# Sensor_Interface.net
KiCad netlist of a schematic drawn in Altium Designer
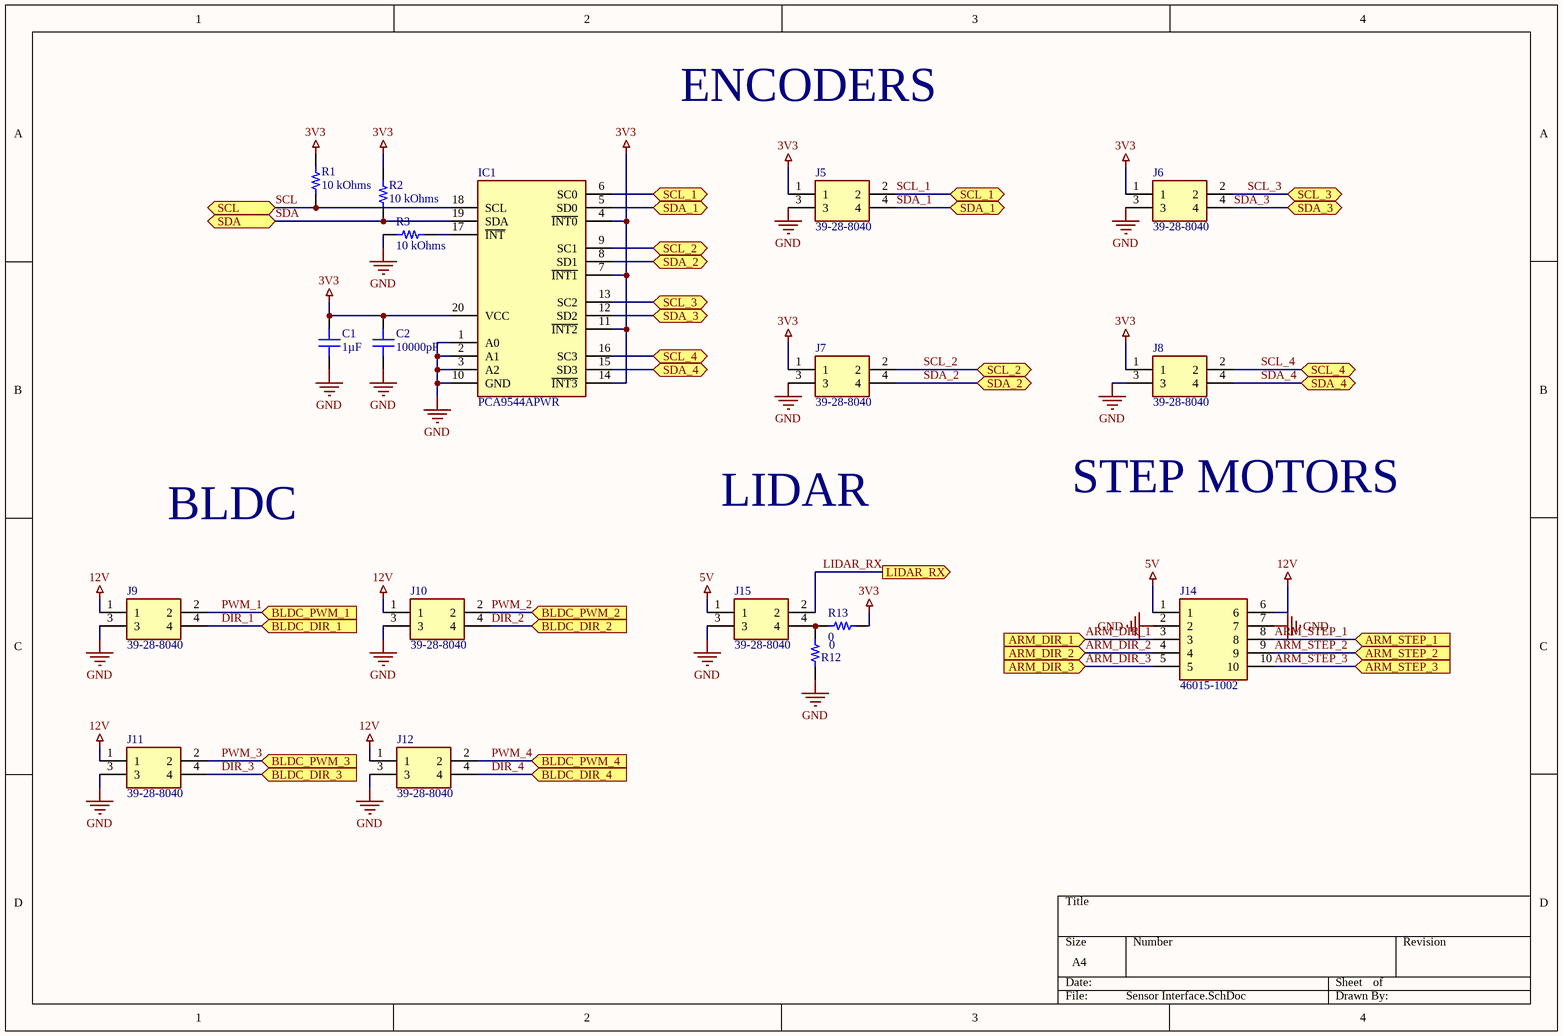
[diagram p0: Sensor Interface.SchDoc]

(export (version "E")
  (design (tool "Eeschema 10.0.6"))
  (components
    (comp (ref "C1")
      (value "1µF")
      (footprint "CAP 0603_1608")
      (description "CAP CER 0603 1UF 16V X7R 10%")
      (fields (field (name "PART NUMBER") "C0603C105K4RACAUTO") (field (name "MANUFACTURER") "KEMET"))
      (libsource (lib "Celestial Altium Library - altium_library") (part "Capacitor"))
    )
    (comp (ref "C2")
      (value "10000pF")
      (footprint "CAP 0603_1608")
      (description "CAP CER 0603 .01UF 16V X7R 20% A")
      (fields (field (name "PART NUMBER") "C0603C103M4RACAUTO") (field (name "MANUFACTURER") "KEMET"))
      (libsource (lib "Celestial Altium Library - altium_library") (part "Capacitor"))
    )
    (comp (ref "IC1")
      (value "PCA9544APWR")
      (footprint "SamacSys:SOP65P640X120-20N")
      (description "Integrated Circuit")
      (fields (field (name "MOUSER PART NUMBER") "595-PCA9544APWR"))
      (libsource (lib "SamacSys") (part "PCA9544APWR"))
    )
    (comp (ref "J5")
      (value "39-28-8040")
      (footprint "SamacSys:RHDR4W125P550X420_2X2_960X960X1310P")
      (description "Connector")
      (fields (field (name "MOUSER PART NUMBER") "538-39-28-8040"))
      (libsource (lib "SamacSys") (part "39-28-8040"))
    )
    (comp (ref "J6")
      (value "39-28-8040")
      (footprint "SamacSys:RHDR4W125P550X420_2X2_960X960X1310P")
      (description "Connector")
      (fields (field (name "MOUSER PART NUMBER") "538-39-28-8040"))
      (libsource (lib "SamacSys") (part "39-28-8040"))
    )
    (comp (ref "J7")
      (value "39-28-8040")
      (footprint "SamacSys:RHDR4W125P550X420_2X2_960X960X1310P")
      (description "Connector")
      (fields (field (name "MOUSER PART NUMBER") "538-39-28-8040"))
      (libsource (lib "SamacSys") (part "39-28-8040"))
    )
    (comp (ref "J8")
      (value "39-28-8040")
      (footprint "SamacSys:RHDR4W125P550X420_2X2_960X960X1310P")
      (description "Connector")
      (fields (field (name "MOUSER PART NUMBER") "538-39-28-8040"))
      (libsource (lib "SamacSys") (part "39-28-8040"))
    )
    (comp (ref "J9")
      (value "39-28-8040")
      (footprint "SamacSys:RHDR4W125P550X420_2X2_960X960X1310P")
      (description "Connector")
      (fields (field (name "MOUSER PART NUMBER") "538-39-28-8040"))
      (libsource (lib "SamacSys") (part "39-28-8040"))
    )
    (comp (ref "J10")
      (value "39-28-8040")
      (footprint "SamacSys:RHDR4W125P550X420_2X2_960X960X1310P")
      (description "Connector")
      (fields (field (name "MOUSER PART NUMBER") "538-39-28-8040"))
      (libsource (lib "SamacSys") (part "39-28-8040"))
    )
    (comp (ref "J11")
      (value "39-28-8040")
      (footprint "SamacSys:RHDR4W125P550X420_2X2_960X960X1310P")
      (description "Connector")
      (fields (field (name "MOUSER PART NUMBER") "538-39-28-8040"))
      (libsource (lib "SamacSys") (part "39-28-8040"))
    )
    (comp (ref "J12")
      (value "39-28-8040")
      (footprint "SamacSys:RHDR4W125P550X420_2X2_960X960X1310P")
      (description "Connector")
      (fields (field (name "MOUSER PART NUMBER") "538-39-28-8040"))
      (libsource (lib "SamacSys") (part "39-28-8040"))
    )
    (comp (ref "J14")
      (value "46015-1002")
      (footprint "SamacSys:460151002")
      (description "Connector")
      (fields (field (name "MOUSER PART NUMBER") "538-46015-1002"))
      (libsource (lib "SamacSys") (part "46015-1002"))
    )
    (comp (ref "J15")
      (value "39-28-8040")
      (footprint "SamacSys:RHDR4W125P550X420_2X2_960X960X1310P")
      (description "Connector")
      (fields (field (name "MOUSER PART NUMBER") "538-39-28-8040"))
      (libsource (lib "SamacSys") (part "39-28-8040"))
    )
    (comp (ref "R1")
      (value "10 kOhms")
      (footprint "RES 0603_1608")
      (description "RES SMD 10K OHM 1% 1/10W 0603")
      (fields (field (name "PART NUMBER") "AF0603FR-0710KL") (field (name "MANUFACTURER") "Yageo"))
      (libsource (lib "Celestial Altium Library - altium_library") (part "Resistor"))
    )
    (comp (ref "R2")
      (value "10 kOhms")
      (footprint "RES 0603_1608")
      (description "RES SMD 10K OHM 1% 1/10W 0603")
      (fields (field (name "PART NUMBER") "AF0603FR-0710KL") (field (name "MANUFACTURER") "Yageo"))
      (libsource (lib "Celestial Altium Library - altium_library") (part "Resistor"))
    )
    (comp (ref "R3")
      (value "10 kOhms")
      (footprint "RES 0603_1608")
      (description "RES SMD 10K OHM 1% 1/10W 0603")
      (fields (field (name "PART NUMBER") "AF0603FR-0710KL") (field (name "MANUFACTURER") "Yageo"))
      (libsource (lib "Celestial Altium Library - altium_library") (part "Resistor"))
    )
    (comp (ref "R12")
      (value "0")
      (footprint "RES 0603_1608")
      (description "RES 0 OHM JUMPER 0603")
      (fields
        (field (name "PART NUMBER") "TLRZ1JTTD")
        (field (name "MANUFACTURER") "KOA Speer Electronics, Inc.")
      )
      (libsource (lib "Celestial Altium Library - altium_library") (part "Resistor"))
    )
    (comp (ref "R13")
      (value "0")
      (footprint "RES 0603_1608")
      (description "RES 0 OHM JUMPER 0603")
      (fields
        (field (name "PART NUMBER") "TLRZ1JTTD")
        (field (name "MANUFACTURER") "KOA Speer Electronics, Inc.")
      )
      (libsource (lib "Celestial Altium Library - altium_library") (part "Resistor"))
    )
  )
  (nets
    (net (code "1") (name "/ARM_DIR_1") (class "Default")
      (node (ref "J14") (pin "3") (pinfunction "3_3") (pintype "passive"))
    )
    (net (code "2") (name "/ARM_DIR_2") (class "Default")
      (node (ref "J14") (pin "4") (pinfunction "4_4") (pintype "passive"))
    )
    (net (code "3") (name "/ARM_DIR_3") (class "Default")
      (node (ref "J14") (pin "5") (pinfunction "5_5") (pintype "passive"))
    )
    (net (code "4") (name "/ARM_STEP_1") (class "Default")
      (node (ref "J14") (pin "8") (pinfunction "8_8") (pintype "passive"))
    )
    (net (code "5") (name "/ARM_STEP_2") (class "Default")
      (node (ref "J14") (pin "9") (pinfunction "9_9") (pintype "passive"))
    )
    (net (code "6") (name "/ARM_STEP_3") (class "Default")
      (node (ref "J14") (pin "10") (pinfunction "10_10") (pintype "passive"))
    )
    (net (code "7") (name "/DIR_1") (class "Default")
      (node (ref "J9") (pin "4") (pinfunction "4_4") (pintype "passive"))
    )
    (net (code "8") (name "/DIR_2") (class "Default")
      (node (ref "J10") (pin "4") (pinfunction "4_4") (pintype "passive"))
    )
    (net (code "9") (name "/DIR_3") (class "Default")
      (node (ref "J11") (pin "4") (pinfunction "4_4") (pintype "passive"))
    )
    (net (code "10") (name "/DIR_4") (class "Default")
      (node (ref "J12") (pin "4") (pinfunction "4_4") (pintype "passive"))
    )
    (net (code "11") (name "/LIDAR_RX") (class "Default")
      (node (ref "J15") (pin "2") (pinfunction "2_2") (pintype "passive"))
    )
    (net (code "12") (name "/PWM_1") (class "Default")
      (node (ref "J9") (pin "2") (pinfunction "2_2") (pintype "passive"))
    )
    (net (code "13") (name "/PWM_2") (class "Default")
      (node (ref "J10") (pin "2") (pinfunction "2_2") (pintype "passive"))
    )
    (net (code "14") (name "/PWM_3") (class "Default")
      (node (ref "J11") (pin "2") (pinfunction "2_2") (pintype "passive"))
    )
    (net (code "15") (name "/PWM_4") (class "Default")
      (node (ref "J12") (pin "2") (pinfunction "2_2") (pintype "passive"))
    )
    (net (code "16") (name "/SCL") (class "Default")
      (node (ref "IC1") (pin "18") (pinfunction "SCL_18") (pintype "passive"))
      (node (ref "R1") (pin "1") (pinfunction "1_1") (pintype "passive"))
    )
    (net (code "17") (name "/SCL_1") (class "Default")
      (node (ref "IC1") (pin "6") (pinfunction "SC0_6") (pintype "passive"))
      (node (ref "J5") (pin "2") (pinfunction "2_2") (pintype "passive"))
    )
    (net (code "18") (name "/SCL_2") (class "Default")
      (node (ref "IC1") (pin "9") (pinfunction "SC1_9") (pintype "passive"))
      (node (ref "J7") (pin "2") (pinfunction "2_2") (pintype "passive"))
    )
    (net (code "19") (name "/SCL_3") (class "Default")
      (node (ref "IC1") (pin "13") (pinfunction "SC2_13") (pintype "passive"))
      (node (ref "J6") (pin "2") (pinfunction "2_2") (pintype "passive"))
    )
    (net (code "20") (name "/SCL_4") (class "Default")
      (node (ref "IC1") (pin "16") (pinfunction "SC3_16") (pintype "passive"))
      (node (ref "J8") (pin "2") (pinfunction "2_2") (pintype "passive"))
    )
    (net (code "21") (name "/SDA") (class "Default")
      (node (ref "IC1") (pin "19") (pinfunction "SDA_19") (pintype "passive"))
      (node (ref "R2") (pin "1") (pinfunction "1_1") (pintype "passive"))
    )
    (net (code "22") (name "/SDA_1") (class "Default")
      (node (ref "IC1") (pin "5") (pinfunction "SD0_5") (pintype "passive"))
      (node (ref "J5") (pin "4") (pinfunction "4_4") (pintype "passive"))
    )
    (net (code "23") (name "/SDA_2") (class "Default")
      (node (ref "IC1") (pin "8") (pinfunction "SD1_8") (pintype "passive"))
      (node (ref "J7") (pin "4") (pinfunction "4_4") (pintype "passive"))
    )
    (net (code "24") (name "/SDA_3") (class "Default")
      (node (ref "IC1") (pin "12") (pinfunction "SD2_12") (pintype "passive"))
      (node (ref "J6") (pin "4") (pinfunction "4_4") (pintype "passive"))
    )
    (net (code "25") (name "/SDA_4") (class "Default")
      (node (ref "IC1") (pin "15") (pinfunction "SD3_15") (pintype "passive"))
      (node (ref "J8") (pin "4") (pinfunction "4_4") (pintype "passive"))
    )
    (net (code "26") (name "3V3") (class "Default")
      (node (ref "C1") (pin "2") (pinfunction "2_2") (pintype "passive"))
      (node (ref "C2") (pin "2") (pinfunction "2_2") (pintype "passive"))
      (node (ref "IC1") (pin "11") (pinfunction "~{INT2}_11") (pintype "passive"))
      (node (ref "IC1") (pin "14") (pinfunction "~{INT3}_14") (pintype "passive"))
      (node (ref "IC1") (pin "20") (pinfunction "VCC_20") (pintype "passive"))
      (node (ref "IC1") (pin "4") (pinfunction "~{INT0}_4") (pintype "passive"))
      (node (ref "IC1") (pin "7") (pinfunction "~{INT1}_7") (pintype "passive"))
      (node (ref "J5") (pin "1") (pinfunction "1_1") (pintype "passive"))
      (node (ref "J6") (pin "1") (pinfunction "1_1") (pintype "passive"))
      (node (ref "J7") (pin "1") (pinfunction "1_1") (pintype "passive"))
      (node (ref "J8") (pin "1") (pinfunction "1_1") (pintype "passive"))
      (node (ref "R1") (pin "2") (pinfunction "2_2") (pintype "passive"))
      (node (ref "R13") (pin "2") (pinfunction "2_2") (pintype "passive"))
      (node (ref "R2") (pin "2") (pinfunction "2_2") (pintype "passive"))
    )
    (net (code "27") (name "5V") (class "Default")
      (node (ref "J14") (pin "1") (pinfunction "1_1") (pintype "passive"))
      (node (ref "J15") (pin "1") (pinfunction "1_1") (pintype "passive"))
    )
    (net (code "28") (name "12V") (class "Default")
      (node (ref "J10") (pin "1") (pinfunction "1_1") (pintype "passive"))
      (node (ref "J11") (pin "1") (pinfunction "1_1") (pintype "passive"))
      (node (ref "J12") (pin "1") (pinfunction "1_1") (pintype "passive"))
      (node (ref "J14") (pin "6") (pinfunction "6_6") (pintype "passive"))
      (node (ref "J9") (pin "1") (pinfunction "1_1") (pintype "passive"))
    )
    (net (code "29") (name "GND") (class "Default")
      (node (ref "C1") (pin "1") (pinfunction "1_1") (pintype "passive"))
      (node (ref "C2") (pin "1") (pinfunction "1_1") (pintype "passive"))
      (node (ref "IC1") (pin "1") (pinfunction "A0_1") (pintype "passive"))
      (node (ref "IC1") (pin "10") (pinfunction "GND_10") (pintype "passive"))
      (node (ref "IC1") (pin "2") (pinfunction "A1_2") (pintype "passive"))
      (node (ref "IC1") (pin "3") (pinfunction "A2_3") (pintype "passive"))
      (node (ref "J10") (pin "3") (pinfunction "3_3") (pintype "passive"))
      (node (ref "J11") (pin "3") (pinfunction "3_3") (pintype "passive"))
      (node (ref "J12") (pin "3") (pinfunction "3_3") (pintype "passive"))
      (node (ref "J14") (pin "2") (pinfunction "2_2") (pintype "passive"))
      (node (ref "J14") (pin "7") (pinfunction "7_7") (pintype "passive"))
      (node (ref "J15") (pin "3") (pinfunction "3_3") (pintype "passive"))
      (node (ref "J5") (pin "3") (pinfunction "3_3") (pintype "passive"))
      (node (ref "J6") (pin "3") (pinfunction "3_3") (pintype "passive"))
      (node (ref "J7") (pin "3") (pinfunction "3_3") (pintype "passive"))
      (node (ref "J8") (pin "3") (pinfunction "3_3") (pintype "passive"))
      (node (ref "J9") (pin "3") (pinfunction "3_3") (pintype "passive"))
      (node (ref "R12") (pin "1") (pinfunction "1_1") (pintype "passive"))
      (node (ref "R3") (pin "1") (pinfunction "1_1") (pintype "passive"))
    )
    (net (code "30") (name "Net-(IC1-~{INT})") (class "Default")
      (node (ref "IC1") (pin "17") (pinfunction "~{INT}_17") (pintype "passive"))
      (node (ref "R3") (pin "2") (pinfunction "2_2") (pintype "passive"))
    )
    (net (code "31") (name "Net-(J15-Pad4)") (class "Default")
      (node (ref "J15") (pin "4") (pinfunction "4_4") (pintype "passive"))
      (node (ref "R12") (pin "2") (pinfunction "2_2") (pintype "passive"))
      (node (ref "R13") (pin "1") (pinfunction "1_1") (pintype "passive"))
    )
  )
)
